# MCU.net
KiCad netlist of a schematic drawn in Altium Designer
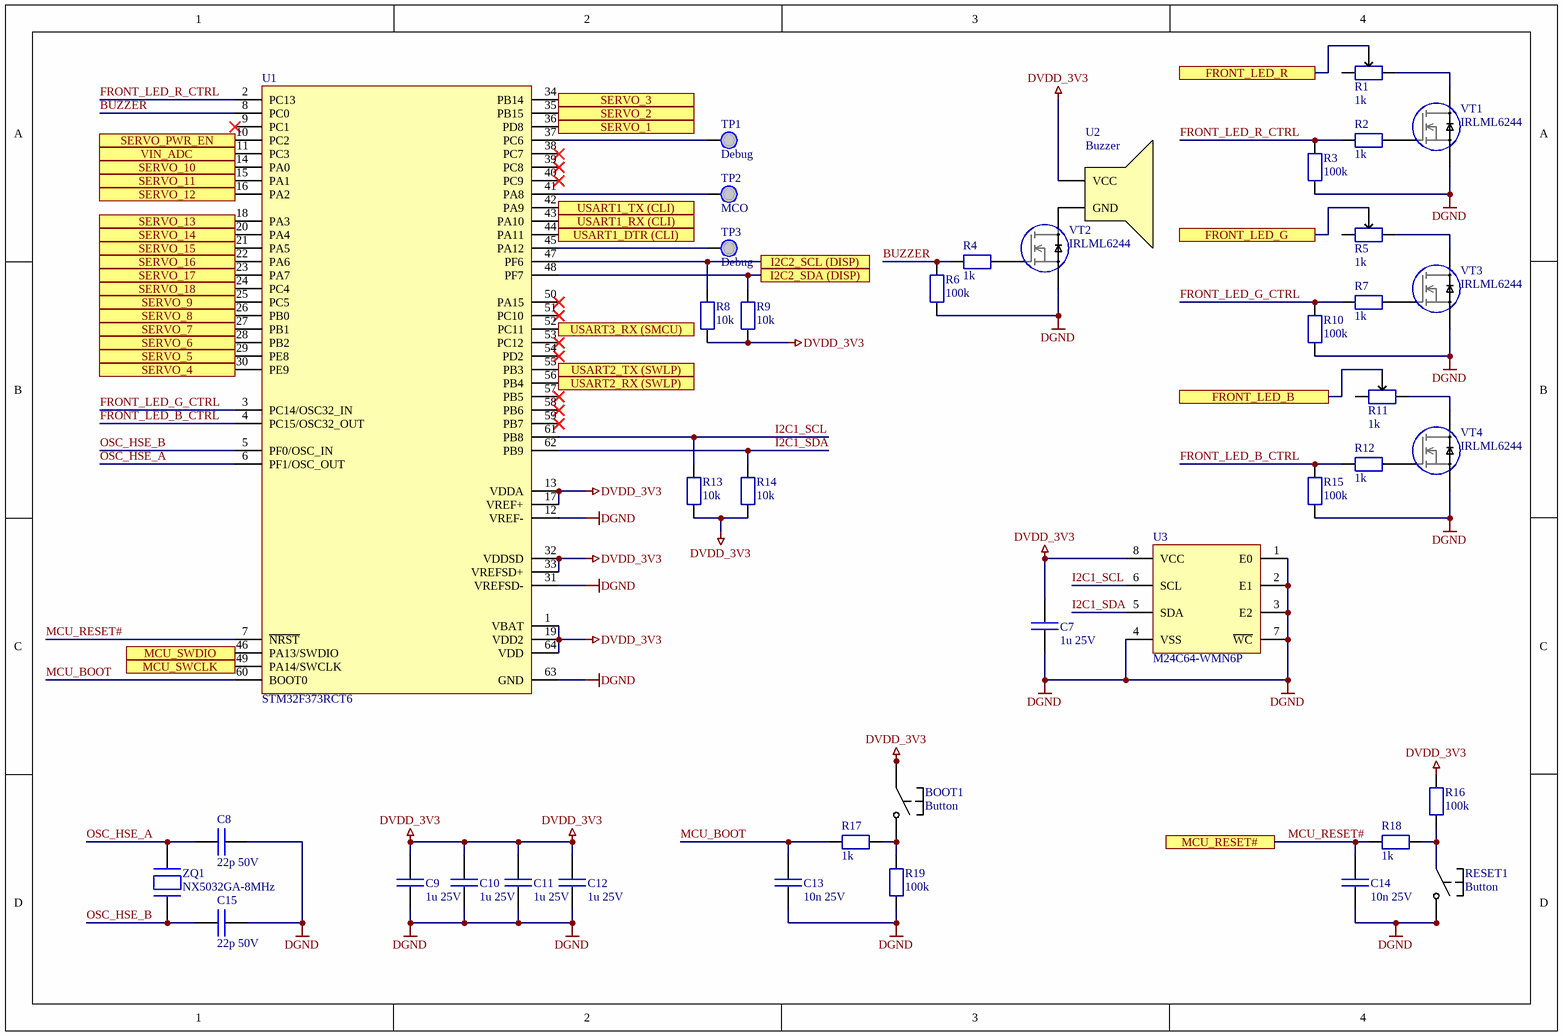
[diagram p0: MCU.SchDoc]

(export (version "E")
  (design (tool "Eeschema 10.0.6"))
  (components
    (comp (ref "BOOT1")
      (value "Button")
      (footprint "BUTTON_SMD_3x6")
      (libsource (lib "controls") (part "Button"))
    )
    (comp (ref "C7")
      (value "1u 25V")
      (footprint "C_0603/1608")
      (description "Non-polarized capacitor")
      (libsource (lib "passive") (part "Capacitor"))
    )
    (comp (ref "C8")
      (value "22p 50V")
      (footprint "C_0603/1608")
      (description "Non-polarized capacitor")
      (libsource (lib "passive") (part "Capacitor"))
    )
    (comp (ref "C9")
      (value "1u 25V")
      (footprint "C_0603/1608")
      (description "Non-polarized capacitor")
      (libsource (lib "passive") (part "Capacitor"))
    )
    (comp (ref "C10")
      (value "1u 25V")
      (footprint "C_0603/1608")
      (description "Non-polarized capacitor")
      (libsource (lib "passive") (part "Capacitor"))
    )
    (comp (ref "C11")
      (value "1u 25V")
      (footprint "C_0603/1608")
      (description "Non-polarized capacitor")
      (libsource (lib "passive") (part "Capacitor"))
    )
    (comp (ref "C12")
      (value "1u 25V")
      (footprint "C_0603/1608")
      (description "Non-polarized capacitor")
      (libsource (lib "passive") (part "Capacitor"))
    )
    (comp (ref "C13")
      (value "10n 25V")
      (footprint "C_0603/1608")
      (description "Non-polarized capacitor")
      (libsource (lib "passive") (part "Capacitor"))
    )
    (comp (ref "C14")
      (value "10n 25V")
      (footprint "C_0603/1608")
      (description "Non-polarized capacitor")
      (libsource (lib "passive") (part "Capacitor"))
    )
    (comp (ref "C15")
      (value "22p 50V")
      (footprint "C_0603/1608")
      (description "Non-polarized capacitor")
      (libsource (lib "passive") (part "Capacitor"))
    )
    (comp (ref "R1")
      (value "1k")
      (footprint "R_VAR_3.2x3.2_SMD")
      (description "Resistor variable")
      (libsource (lib "passive") (part "Resistor variable"))
    )
    (comp (ref "R2")
      (value "1k")
      (footprint "R_0603/1608")
      (description "Resistor")
      (libsource (lib "passive") (part "Resistor"))
    )
    (comp (ref "R3")
      (value "100k")
      (footprint "R_0603/1608")
      (description "Resistor")
      (libsource (lib "passive") (part "Resistor"))
    )
    (comp (ref "R4")
      (value "1k")
      (footprint "R_0603/1608")
      (description "Resistor")
      (libsource (lib "passive") (part "Resistor"))
    )
    (comp (ref "R5")
      (value "1k")
      (footprint "R_VAR_3.2x3.2_SMD")
      (description "Resistor variable")
      (libsource (lib "passive") (part "Resistor variable"))
    )
    (comp (ref "R6")
      (value "100k")
      (footprint "R_0603/1608")
      (description "Resistor")
      (libsource (lib "passive") (part "Resistor"))
    )
    (comp (ref "R7")
      (value "1k")
      (footprint "R_0603/1608")
      (description "Resistor")
      (libsource (lib "passive") (part "Resistor"))
    )
    (comp (ref "R8")
      (value "10k")
      (footprint "R_0603/1608")
      (description "Resistor")
      (libsource (lib "passive") (part "Resistor"))
    )
    (comp (ref "R9")
      (value "10k")
      (footprint "R_0603/1608")
      (description "Resistor")
      (libsource (lib "passive") (part "Resistor"))
    )
    (comp (ref "R10")
      (value "100k")
      (footprint "R_0603/1608")
      (description "Resistor")
      (libsource (lib "passive") (part "Resistor"))
    )
    (comp (ref "R11")
      (value "1k")
      (footprint "R_VAR_3.2x3.2_SMD")
      (description "Resistor variable")
      (libsource (lib "passive") (part "Resistor variable"))
    )
    (comp (ref "R12")
      (value "1k")
      (footprint "R_0603/1608")
      (description "Resistor")
      (libsource (lib "passive") (part "Resistor"))
    )
    (comp (ref "R13")
      (value "10k")
      (footprint "R_0603/1608")
      (description "Resistor")
      (libsource (lib "passive") (part "Resistor"))
    )
    (comp (ref "R14")
      (value "10k")
      (footprint "R_0603/1608")
      (description "Resistor")
      (libsource (lib "passive") (part "Resistor"))
    )
    (comp (ref "R15")
      (value "100k")
      (footprint "R_0603/1608")
      (description "Resistor")
      (libsource (lib "passive") (part "Resistor"))
    )
    (comp (ref "R16")
      (value "100k")
      (footprint "R_0603/1608")
      (description "Resistor")
      (libsource (lib "passive") (part "Resistor"))
    )
    (comp (ref "R17")
      (value "1k")
      (footprint "R_0603/1608")
      (description "Resistor")
      (libsource (lib "passive") (part "Resistor"))
    )
    (comp (ref "R18")
      (value "1k")
      (footprint "R_0603/1608")
      (description "Resistor")
      (libsource (lib "passive") (part "Resistor"))
    )
    (comp (ref "R19")
      (value "100k")
      (footprint "R_0603/1608")
      (description "Resistor")
      (libsource (lib "passive") (part "Resistor"))
    )
    (comp (ref "RESET1")
      (value "Button")
      (footprint "BUTTON_SMD_3x6")
      (libsource (lib "controls") (part "Button"))
    )
    (comp (ref "TP1")
      (value "Debug")
      (footprint "TP_SMD_D1.00")
      (description "Test point")
      (libsource (lib "connectors") (part "Test point"))
    )
    (comp (ref "TP2")
      (value "MCO")
      (footprint "TP_SMD_D1.00")
      (description "Test point")
      (libsource (lib "connectors") (part "Test point"))
    )
    (comp (ref "TP3")
      (value "Debug")
      (footprint "TP_SMD_D1.00")
      (description "Test point")
      (libsource (lib "connectors") (part "Test point"))
    )
    (comp (ref "U1")
      (value "STM32F373RCT6")
      (footprint "LQFP64")
      (description "32-bit Cortex-M3")
      (libsource (lib "MCU and memory") (part "STM32F373R"))
    )
    (comp (ref "U2") (value "Buzzer") (footprint "PLS-2R 2.54") (libsource (lib "devices") (part "Buzzer")))
    (comp (ref "U3")
      (value "M24C64-WMN6P")
      (footprint "SO8_1.27")
      (description "I2C EEPROM")
      (libsource (lib "MCU and memory") (part "I2C EEPROM"))
    )
    (comp (ref "VT1")
      (value "IRLML6244")
      (footprint "SOT23-3")
      (description "MOSFET N")
      (libsource (lib "active") (part "MOSFET N"))
    )
    (comp (ref "VT2")
      (value "IRLML6244")
      (footprint "SOT23-3")
      (description "MOSFET N")
      (libsource (lib "active") (part "MOSFET N"))
    )
    (comp (ref "VT3")
      (value "IRLML6244")
      (footprint "SOT23-3")
      (description "MOSFET N")
      (libsource (lib "active") (part "MOSFET N"))
    )
    (comp (ref "VT4")
      (value "IRLML6244")
      (footprint "SOT23-3")
      (description "MOSFET N")
      (libsource (lib "active") (part "MOSFET N"))
    )
    (comp (ref "ZQ1")
      (value "NX5032GA-8MHz")
      (footprint "OSC_2PINS SMD")
      (description "Crystal oscillator")
      (libsource (lib "passive") (part "Crystal oscillator"))
    )
  )
  (nets
    (net (code "1") (name "/BUZZER") (class "Default")
      (node (ref "R4") (pin "2") (pintype "passive"))
      (node (ref "R6") (pin "2") (pintype "passive"))
      (node (ref "U1") (pin "8") (pinfunction "PC0_8") (pintype "passive"))
    )
    (net (code "2") (name "/FRONT_LED_B") (class "Default") (node (ref "R11") (pin "2") (pintype "passive")))
    (net (code "3") (name "/FRONT_LED_B_CTRL") (class "Default")
      (node (ref "R12") (pin "2") (pintype "passive"))
      (node (ref "R15") (pin "2") (pintype "passive"))
      (node (ref "U1") (pin "4") (pinfunction "PC15/OSC32_OUT_4") (pintype "passive"))
    )
    (net (code "4") (name "/FRONT_LED_G") (class "Default") (node (ref "R5") (pin "2") (pintype "passive")))
    (net (code "5") (name "/FRONT_LED_G_CTRL") (class "Default")
      (node (ref "R10") (pin "2") (pintype "passive"))
      (node (ref "R7") (pin "2") (pintype "passive"))
      (node (ref "U1") (pin "3") (pinfunction "PC14/OSC32_IN_3") (pintype "passive"))
    )
    (net (code "6") (name "/FRONT_LED_R") (class "Default") (node (ref "R1") (pin "2") (pintype "passive")))
    (net (code "7") (name "/FRONT_LED_R_CTRL") (class "Default")
      (node (ref "R2") (pin "2") (pintype "passive"))
      (node (ref "R3") (pin "2") (pintype "passive"))
      (node (ref "U1") (pin "2") (pinfunction "PC13_2") (pintype "passive"))
    )
    (net (code "8") (name "/I2C1_SCL") (class "Default")
      (node (ref "R13") (pin "2") (pintype "passive"))
      (node (ref "U1") (pin "61") (pinfunction "PB8_61") (pintype "passive"))
      (node (ref "U3") (pin "6") (pinfunction "SCL_6") (pintype "passive"))
    )
    (net (code "9") (name "/I2C1_SDA") (class "Default")
      (node (ref "R14") (pin "2") (pintype "passive"))
      (node (ref "U1") (pin "62") (pinfunction "PB9_62") (pintype "passive"))
      (node (ref "U3") (pin "5") (pinfunction "SDA_5") (pintype "passive"))
    )
    (net (code "10") (name "/I2C2_SCL (DISP)") (class "Default")
      (node (ref "R8") (pin "2") (pintype "passive"))
      (node (ref "U1") (pin "47") (pinfunction "PF6_47") (pintype "passive"))
    )
    (net (code "11") (name "/I2C2_SDA (DISP)") (class "Default")
      (node (ref "R9") (pin "2") (pintype "passive"))
      (node (ref "U1") (pin "48") (pinfunction "PF7_48") (pintype "passive"))
    )
    (net (code "12") (name "/MCU_BOOT") (class "Default")
      (node (ref "C13") (pin "1") (pintype "passive"))
      (node (ref "R17") (pin "2") (pintype "passive"))
      (node (ref "U1") (pin "60") (pinfunction "BOOT0_60") (pintype "passive"))
    )
    (net (code "13") (name "/MCU_RESET#") (class "Default")
      (node (ref "C14") (pin "1") (pintype "passive"))
      (node (ref "R18") (pin "2") (pintype "passive"))
      (node (ref "U1") (pin "7") (pinfunction "~{NRST}_7") (pintype "passive"))
    )
    (net (code "14") (name "/MCU_SWCLK") (class "Default")
      (node (ref "U1") (pin "49") (pinfunction "PA14/SWCLK_49") (pintype "passive"))
    )
    (net (code "15") (name "/MCU_SWDIO") (class "Default")
      (node (ref "U1") (pin "46") (pinfunction "PA13/SWDIO_46") (pintype "passive"))
    )
    (net (code "16") (name "/OSC_HSE_A") (class "Default")
      (node (ref "C8") (pin "1") (pintype "passive"))
      (node (ref "U1") (pin "6") (pinfunction "PF1/OSC_OUT_6") (pintype "passive"))
      (node (ref "ZQ1") (pin "2") (pintype "passive"))
    )
    (net (code "17") (name "/OSC_HSE_B") (class "Default")
      (node (ref "C15") (pin "1") (pintype "passive"))
      (node (ref "U1") (pin "5") (pinfunction "PF0/OSC_IN_5") (pintype "passive"))
      (node (ref "ZQ1") (pin "1") (pintype "passive"))
    )
    (net (code "18") (name "/SERVO_1") (class "Default")
      (node (ref "U1") (pin "36") (pinfunction "PD8_36") (pintype "passive"))
    )
    (net (code "19") (name "/SERVO_2") (class "Default")
      (node (ref "U1") (pin "35") (pinfunction "PB15_35") (pintype "passive"))
    )
    (net (code "20") (name "/SERVO_3") (class "Default")
      (node (ref "U1") (pin "34") (pinfunction "PB14_34") (pintype "passive"))
    )
    (net (code "21") (name "/SERVO_4") (class "Default")
      (node (ref "U1") (pin "30") (pinfunction "PE9_30") (pintype "passive"))
    )
    (net (code "22") (name "/SERVO_5") (class "Default")
      (node (ref "U1") (pin "29") (pinfunction "PE8_29") (pintype "passive"))
    )
    (net (code "23") (name "/SERVO_6") (class "Default")
      (node (ref "U1") (pin "28") (pinfunction "PB2_28") (pintype "passive"))
    )
    (net (code "24") (name "/SERVO_7") (class "Default")
      (node (ref "U1") (pin "27") (pinfunction "PB1_27") (pintype "passive"))
    )
    (net (code "25") (name "/SERVO_8") (class "Default")
      (node (ref "U1") (pin "26") (pinfunction "PB0_26") (pintype "passive"))
    )
    (net (code "26") (name "/SERVO_9") (class "Default")
      (node (ref "U1") (pin "25") (pinfunction "PC5_25") (pintype "passive"))
    )
    (net (code "27") (name "/SERVO_10") (class "Default")
      (node (ref "U1") (pin "14") (pinfunction "PA0_14") (pintype "passive"))
    )
    (net (code "28") (name "/SERVO_11") (class "Default")
      (node (ref "U1") (pin "15") (pinfunction "PA1_15") (pintype "passive"))
    )
    (net (code "29") (name "/SERVO_12") (class "Default")
      (node (ref "U1") (pin "16") (pinfunction "PA2_16") (pintype "passive"))
    )
    (net (code "30") (name "/SERVO_13") (class "Default")
      (node (ref "U1") (pin "18") (pinfunction "PA3_18") (pintype "passive"))
    )
    (net (code "31") (name "/SERVO_14") (class "Default")
      (node (ref "U1") (pin "20") (pinfunction "PA4_20") (pintype "passive"))
    )
    (net (code "32") (name "/SERVO_15") (class "Default")
      (node (ref "U1") (pin "21") (pinfunction "PA5_21") (pintype "passive"))
    )
    (net (code "33") (name "/SERVO_16") (class "Default")
      (node (ref "U1") (pin "22") (pinfunction "PA6_22") (pintype "passive"))
    )
    (net (code "34") (name "/SERVO_17") (class "Default")
      (node (ref "U1") (pin "23") (pinfunction "PA7_23") (pintype "passive"))
    )
    (net (code "35") (name "/SERVO_18") (class "Default")
      (node (ref "U1") (pin "24") (pinfunction "PC4_24") (pintype "passive"))
    )
    (net (code "36") (name "/SERVO_PWR_EN") (class "Default")
      (node (ref "U1") (pin "10") (pinfunction "PC2_10") (pintype "passive"))
    )
    (net (code "37") (name "/USART1_DTR (CLI)") (class "Default")
      (node (ref "U1") (pin "44") (pinfunction "PA11_44") (pintype "passive"))
    )
    (net (code "38") (name "/USART1_RX (CLI)") (class "Default")
      (node (ref "U1") (pin "43") (pinfunction "PA10_43") (pintype "passive"))
    )
    (net (code "39") (name "/USART1_TX (CLI)") (class "Default")
      (node (ref "U1") (pin "42") (pinfunction "PA9_42") (pintype "passive"))
    )
    (net (code "40") (name "/USART2_RX (SWLP)") (class "Default")
      (node (ref "U1") (pin "56") (pinfunction "PB4_56") (pintype "passive"))
    )
    (net (code "41") (name "/USART2_TX (SWLP)") (class "Default")
      (node (ref "U1") (pin "55") (pinfunction "PB3_55") (pintype "passive"))
    )
    (net (code "42") (name "/USART3_RX (SMCU)") (class "Default")
      (node (ref "U1") (pin "52") (pinfunction "PC11_52") (pintype "passive"))
    )
    (net (code "43") (name "/VIN_ADC") (class "Default")
      (node (ref "U1") (pin "11") (pinfunction "PC3_11") (pintype "passive"))
    )
    (net (code "44") (name "DGND") (class "Default")
      (node (ref "C10") (pin "2") (pintype "passive"))
      (node (ref "C11") (pin "2") (pintype "passive"))
      (node (ref "C12") (pin "2") (pintype "passive"))
      (node (ref "C13") (pin "2") (pintype "passive"))
      (node (ref "C14") (pin "2") (pintype "passive"))
      (node (ref "C15") (pin "2") (pintype "passive"))
      (node (ref "C7") (pin "1") (pintype "passive"))
      (node (ref "C8") (pin "2") (pintype "passive"))
      (node (ref "C9") (pin "2") (pintype "passive"))
      (node (ref "R10") (pin "1") (pintype "passive"))
      (node (ref "R15") (pin "1") (pintype "passive"))
      (node (ref "R19") (pin "2") (pintype "passive"))
      (node (ref "R3") (pin "1") (pintype "passive"))
      (node (ref "R6") (pin "1") (pintype "passive"))
      (node (ref "RESET1") (pin "2") (pinfunction "2_2") (pintype "passive"))
      (node (ref "RESET1") (pin "4") (pinfunction "4_4") (pintype "passive"))
      (node (ref "U1") (pin "12") (pinfunction "VREF-_12") (pintype "passive"))
      (node (ref "U1") (pin "31") (pinfunction "VREFSD-_31") (pintype "passive"))
      (node (ref "U1") (pin "63") (pinfunction "GND_63") (pintype "passive"))
      (node (ref "U3") (pin "1") (pinfunction "E0_1") (pintype "passive"))
      (node (ref "U3") (pin "2") (pinfunction "E1_2") (pintype "passive"))
      (node (ref "U3") (pin "3") (pinfunction "E2_3") (pintype "passive"))
      (node (ref "U3") (pin "4") (pinfunction "VSS_4") (pintype "passive"))
      (node (ref "U3") (pin "7") (pinfunction "~{WC}_7") (pintype "passive"))
      (node (ref "VT1") (pin "S") (pintype "passive"))
      (node (ref "VT2") (pin "S") (pintype "passive"))
      (node (ref "VT3") (pin "S") (pintype "passive"))
      (node (ref "VT4") (pin "S") (pintype "passive"))
    )
    (net (code "45") (name "DVDD_3V3") (class "Default")
      (node (ref "BOOT1") (pin "1") (pinfunction "1_1") (pintype "passive"))
      (node (ref "BOOT1") (pin "3") (pinfunction "3_3") (pintype "passive"))
      (node (ref "C10") (pin "1") (pintype "passive"))
      (node (ref "C11") (pin "1") (pintype "passive"))
      (node (ref "C12") (pin "1") (pintype "passive"))
      (node (ref "C7") (pin "2") (pintype "passive"))
      (node (ref "C9") (pin "1") (pintype "passive"))
      (node (ref "R13") (pin "1") (pintype "passive"))
      (node (ref "R14") (pin "1") (pintype "passive"))
      (node (ref "R16") (pin "1") (pintype "passive"))
      (node (ref "R8") (pin "1") (pintype "passive"))
      (node (ref "R9") (pin "1") (pintype "passive"))
      (node (ref "U1") (pin "1") (pinfunction "VBAT_1") (pintype "passive"))
      (node (ref "U1") (pin "13") (pinfunction "VDDA_13") (pintype "passive"))
      (node (ref "U1") (pin "17") (pinfunction "VREF+_17") (pintype "passive"))
      (node (ref "U1") (pin "19") (pinfunction "VDD2_19") (pintype "passive"))
      (node (ref "U1") (pin "32") (pinfunction "VDDSD_32") (pintype "passive"))
      (node (ref "U1") (pin "33") (pinfunction "VREFSD+_33") (pintype "passive"))
      (node (ref "U1") (pin "64") (pinfunction "VDD_64") (pintype "passive"))
      (node (ref "U2") (pin "2") (pinfunction "VCC_2") (pintype "passive"))
      (node (ref "U3") (pin "8") (pinfunction "VCC_8") (pintype "passive"))
    )
    (net (code "46") (name "Net-(BOOT1-Pad2)") (class "Default")
      (node (ref "BOOT1") (pin "2") (pinfunction "2_2") (pintype "passive"))
      (node (ref "BOOT1") (pin "4") (pinfunction "4_4") (pintype "passive"))
      (node (ref "R17") (pin "1") (pintype "passive"))
      (node (ref "R19") (pin "1") (pintype "passive"))
    )
    (net (code "47") (name "Net-(R1-Pad3)") (class "Default")
      (node (ref "R1") (pin "3") (pintype "passive"))
      (node (ref "VT1") (pin "D") (pintype "passive"))
    )
    (net (code "48") (name "Net-(R2-Pad1)") (class "Default")
      (node (ref "R2") (pin "1") (pintype "passive"))
      (node (ref "VT1") (pin "G") (pintype "passive"))
    )
    (net (code "49") (name "Net-(R4-Pad1)") (class "Default")
      (node (ref "R4") (pin "1") (pintype "passive"))
      (node (ref "VT2") (pin "G") (pintype "passive"))
    )
    (net (code "50") (name "Net-(R5-Pad3)") (class "Default")
      (node (ref "R5") (pin "3") (pintype "passive"))
      (node (ref "VT3") (pin "D") (pintype "passive"))
    )
    (net (code "51") (name "Net-(R7-Pad1)") (class "Default")
      (node (ref "R7") (pin "1") (pintype "passive"))
      (node (ref "VT3") (pin "G") (pintype "passive"))
    )
    (net (code "52") (name "Net-(R11-Pad3)") (class "Default")
      (node (ref "R11") (pin "3") (pintype "passive"))
      (node (ref "VT4") (pin "D") (pintype "passive"))
    )
    (net (code "53") (name "Net-(R12-Pad1)") (class "Default")
      (node (ref "R12") (pin "1") (pintype "passive"))
      (node (ref "VT4") (pin "G") (pintype "passive"))
    )
    (net (code "54") (name "Net-(R16-Pad2)") (class "Default")
      (node (ref "R16") (pin "2") (pintype "passive"))
      (node (ref "R18") (pin "1") (pintype "passive"))
      (node (ref "RESET1") (pin "1") (pinfunction "1_1") (pintype "passive"))
      (node (ref "RESET1") (pin "3") (pinfunction "3_3") (pintype "passive"))
    )
    (net (code "55") (name "Net-(U1-PA8)") (class "Default")
      (node (ref "TP2") (pin "1") (pintype "passive"))
      (node (ref "U1") (pin "41") (pinfunction "PA8_41") (pintype "passive"))
    )
    (net (code "56") (name "Net-(U1-PA12)") (class "Default")
      (node (ref "TP3") (pin "1") (pintype "passive"))
      (node (ref "U1") (pin "45") (pinfunction "PA12_45") (pintype "passive"))
    )
    (net (code "57") (name "Net-(U1-PC6)") (class "Default")
      (node (ref "TP1") (pin "1") (pintype "passive"))
      (node (ref "U1") (pin "37") (pinfunction "PC6_37") (pintype "passive"))
    )
    (net (code "58") (name "Net-(U2-GND)") (class "Default")
      (node (ref "U2") (pin "1") (pinfunction "GND_1") (pintype "passive"))
      (node (ref "VT2") (pin "D") (pintype "passive"))
    )
    (net (code "59") (name "unconnected-(R1-Pad1)") (class "Default")
      (node (ref "R1") (pin "1") (pintype "passive"))
    )
    (net (code "60") (name "unconnected-(R5-Pad1)") (class "Default")
      (node (ref "R5") (pin "1") (pintype "passive"))
    )
    (net (code "61") (name "unconnected-(R11-Pad1)") (class "Default")
      (node (ref "R11") (pin "1") (pintype "passive"))
    )
    (net (code "62") (name "unconnected-(U1-EP-Pad0)") (class "Default")
      (node (ref "U1") (pin "0") (pinfunction "EP_0") (pintype "passive"))
    )
    (net (code "63") (name "unconnected-(U1-PA15-Pad50)") (class "Default")
      (node (ref "U1") (pin "50") (pinfunction "PA15_50") (pintype "passive+no_connect"))
    )
    (net (code "64") (name "unconnected-(U1-PB5-Pad57)") (class "Default")
      (node (ref "U1") (pin "57") (pinfunction "PB5_57") (pintype "passive+no_connect"))
    )
    (net (code "65") (name "unconnected-(U1-PB6-Pad58)") (class "Default")
      (node (ref "U1") (pin "58") (pinfunction "PB6_58") (pintype "passive+no_connect"))
    )
    (net (code "66") (name "unconnected-(U1-PB7-Pad59)") (class "Default")
      (node (ref "U1") (pin "59") (pinfunction "PB7_59") (pintype "passive+no_connect"))
    )
    (net (code "67") (name "unconnected-(U1-PC1-Pad9)") (class "Default")
      (node (ref "U1") (pin "9") (pinfunction "PC1_9") (pintype "passive+no_connect"))
    )
    (net (code "68") (name "unconnected-(U1-PC7-Pad38)") (class "Default")
      (node (ref "U1") (pin "38") (pinfunction "PC7_38") (pintype "passive+no_connect"))
    )
    (net (code "69") (name "unconnected-(U1-PC8-Pad39)") (class "Default")
      (node (ref "U1") (pin "39") (pinfunction "PC8_39") (pintype "passive+no_connect"))
    )
    (net (code "70") (name "unconnected-(U1-PC9-Pad40)") (class "Default")
      (node (ref "U1") (pin "40") (pinfunction "PC9_40") (pintype "passive+no_connect"))
    )
    (net (code "71") (name "unconnected-(U1-PC10-Pad51)") (class "Default")
      (node (ref "U1") (pin "51") (pinfunction "PC10_51") (pintype "passive+no_connect"))
    )
    (net (code "72") (name "unconnected-(U1-PC12-Pad53)") (class "Default")
      (node (ref "U1") (pin "53") (pinfunction "PC12_53") (pintype "passive+no_connect"))
    )
    (net (code "73") (name "unconnected-(U1-PD2-Pad54)") (class "Default")
      (node (ref "U1") (pin "54") (pinfunction "PD2_54") (pintype "passive+no_connect"))
    )
  )
)
